# 505_outin_kinoma.net
KiCad netlist of a schematic drawn in EAGLE
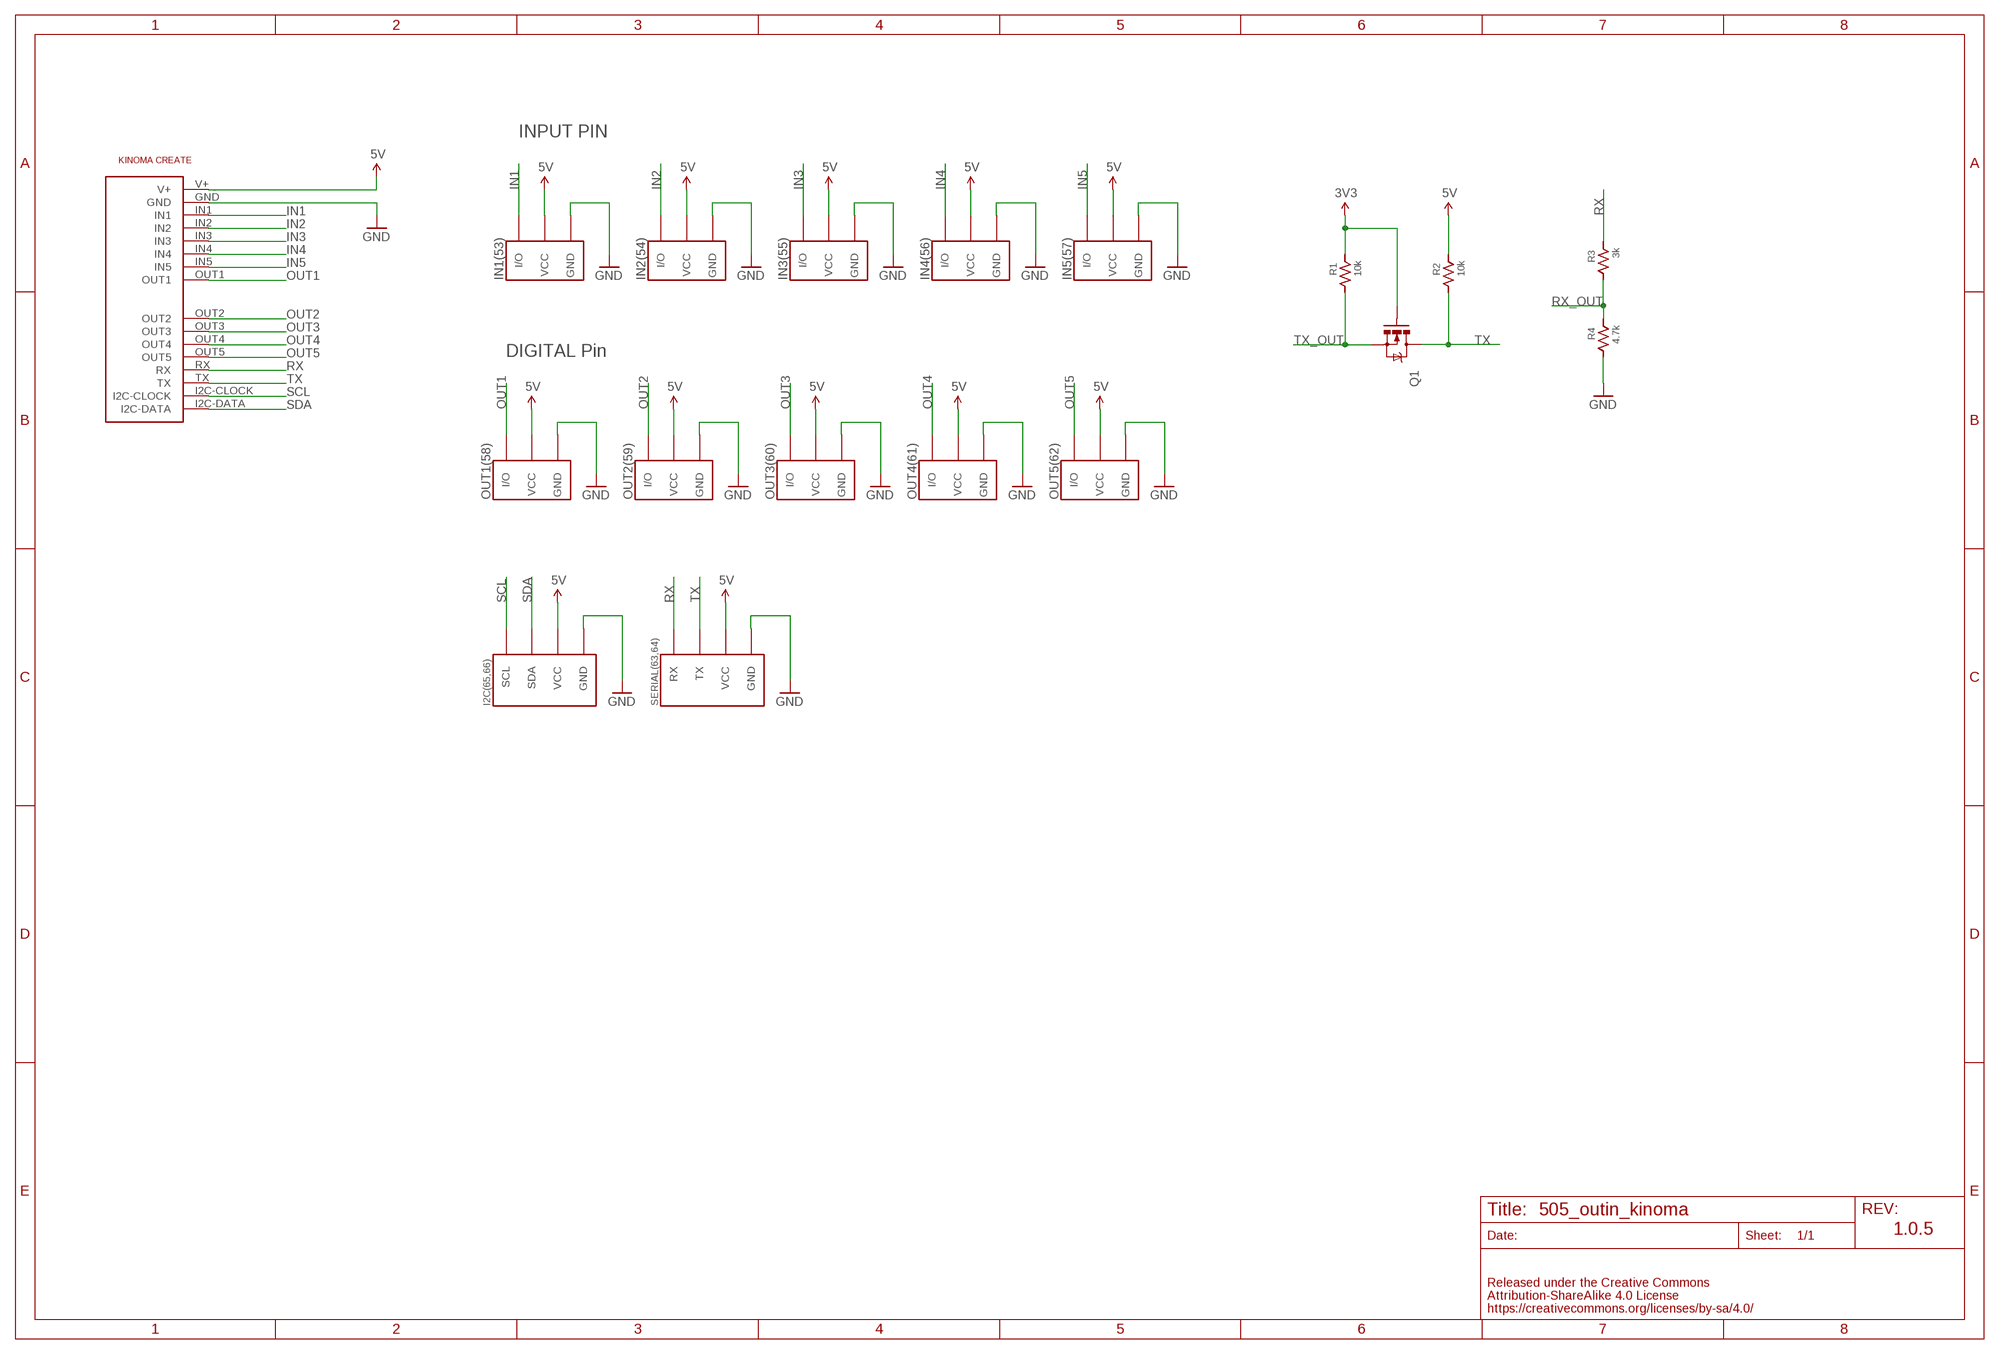
[diagram p0: schematic, sheet 1]

(export (version "E")
  (design (tool "Eeschema 10.0.6"))
  (components
    (comp (ref "I2C(65,66)")
      (value "I2C")
      (footprint "eagle-import:FABO_BRICK_I2C_S04B-PASK-2")
      (libsource (lib "eagle-import") (part "FABO_BRICK_I2C-S04B-PASK-2"))
    )
    (comp (ref "IN1(53)")
      (value "FABO_BRICK_3PIN-B03B-PASK-1")
      (footprint "eagle-import:FABO_BRICK_3PIN_B03B-PASK-1")
      (libsource (lib "eagle-import") (part "FABO_BRICK_3PIN-B03B-PASK-1"))
    )
    (comp (ref "IN2(54)")
      (value "FABO_BRICK_3PIN-B03B-PASK-1")
      (footprint "eagle-import:FABO_BRICK_3PIN_B03B-PASK-1")
      (libsource (lib "eagle-import") (part "FABO_BRICK_3PIN-B03B-PASK-1"))
    )
    (comp (ref "IN3(55)")
      (value "FABO_BRICK_3PIN-B03B-PASK-1")
      (footprint "eagle-import:FABO_BRICK_3PIN_B03B-PASK-1")
      (libsource (lib "eagle-import") (part "FABO_BRICK_3PIN-B03B-PASK-1"))
    )
    (comp (ref "IN4(56)")
      (value "FABO_BRICK_3PIN-B03B-PASK-1")
      (footprint "eagle-import:FABO_BRICK_3PIN_B03B-PASK-1")
      (libsource (lib "eagle-import") (part "FABO_BRICK_3PIN-B03B-PASK-1"))
    )
    (comp (ref "IN5(57)")
      (value "FABO_BRICK_3PIN-B03B-PASK-1")
      (footprint "eagle-import:FABO_BRICK_3PIN_B03B-PASK-1")
      (libsource (lib "eagle-import") (part "FABO_BRICK_3PIN-B03B-PASK-1"))
    )
    (comp (ref "OUT1(58)")
      (value "FABO_BRICK_3PIN-B03B-PASK-1")
      (footprint "eagle-import:FABO_BRICK_3PIN_B03B-PASK-1")
      (libsource (lib "eagle-import") (part "FABO_BRICK_3PIN-B03B-PASK-1"))
    )
    (comp (ref "OUT2(59)")
      (value "FABO_BRICK_3PIN-B03B-PASK-1")
      (footprint "eagle-import:FABO_BRICK_3PIN_B03B-PASK-1")
      (libsource (lib "eagle-import") (part "FABO_BRICK_3PIN-B03B-PASK-1"))
    )
    (comp (ref "OUT3(60)")
      (value "FABO_BRICK_3PIN-B03B-PASK-1")
      (footprint "eagle-import:FABO_BRICK_3PIN_B03B-PASK-1")
      (libsource (lib "eagle-import") (part "FABO_BRICK_3PIN-B03B-PASK-1"))
    )
    (comp (ref "OUT4(61)")
      (value "FABO_BRICK_3PIN-B03B-PASK-1")
      (footprint "eagle-import:FABO_BRICK_3PIN_B03B-PASK-1")
      (libsource (lib "eagle-import") (part "FABO_BRICK_3PIN-B03B-PASK-1"))
    )
    (comp (ref "OUT5(62)")
      (value "FABO_BRICK_3PIN-B03B-PASK-1")
      (footprint "eagle-import:FABO_BRICK_3PIN_B03B-PASK-1")
      (libsource (lib "eagle-import") (part "FABO_BRICK_3PIN-B03B-PASK-1"))
    )
    (comp (ref "Q1")
      (value "MOSFET-N-BSS138")
      (footprint "eagle-import:SOT23-3")
      (libsource (lib "eagle-import") (part "MOSFET-N-BSS138"))
    )
    (comp (ref "R1")
      (value "10k")
      (footprint "eagle-import:0402")
      (libsource (lib "eagle-import") (part "RESISTOR-0402"))
    )
    (comp (ref "R2")
      (value "10k")
      (footprint "eagle-import:0402")
      (libsource (lib "eagle-import") (part "RESISTOR-0402"))
    )
    (comp (ref "R3")
      (value "3k")
      (footprint "eagle-import:0402")
      (libsource (lib "eagle-import") (part "RESISTOR-0402"))
    )
    (comp (ref "R4")
      (value "4.7k")
      (footprint "eagle-import:0402")
      (libsource (lib "eagle-import") (part "RESISTOR-0402"))
    )
    (comp (ref "SERIAL(63,64)")
      (value "FABO_BRICK_SERIAL-S04B-PASK-2")
      (footprint "eagle-import:FABO_BRICK_SERIAL_S04B-PASK-2")
      (libsource (lib "eagle-import") (part "FABO_BRICK_SERIAL-S04B-PASK-2"))
    )
    (comp (ref "U$18")
      (value "FABO-KINOMA")
      (footprint "eagle-import:FABO-KINOMA")
      (libsource (lib "eagle-import") (part "FABO-KINOMA"))
    )
  )
  (nets
    (net (code "1") (name "/IN1") (class "Default")
      (node (ref "IN1(53)") (pin "I/O") (pinfunction "I/O_I/O") (pintype "bidirectional"))
      (node (ref "U$18") (pin "IN1") (pinfunction "IN1_IN1") (pintype "bidirectional"))
    )
    (net (code "2") (name "/IN2") (class "Default")
      (node (ref "IN2(54)") (pin "I/O") (pinfunction "I/O_I/O") (pintype "bidirectional"))
      (node (ref "U$18") (pin "IN2") (pinfunction "IN2_IN2") (pintype "bidirectional"))
    )
    (net (code "3") (name "/IN3") (class "Default")
      (node (ref "IN3(55)") (pin "I/O") (pinfunction "I/O_I/O") (pintype "bidirectional"))
      (node (ref "U$18") (pin "IN3") (pinfunction "IN3_IN3") (pintype "bidirectional"))
    )
    (net (code "4") (name "/IN4") (class "Default")
      (node (ref "IN4(56)") (pin "I/O") (pinfunction "I/O_I/O") (pintype "bidirectional"))
      (node (ref "U$18") (pin "IN4") (pinfunction "IN4_IN4") (pintype "bidirectional"))
    )
    (net (code "5") (name "/IN5") (class "Default")
      (node (ref "IN5(57)") (pin "I/O") (pinfunction "I/O_I/O") (pintype "bidirectional"))
      (node (ref "U$18") (pin "IN5") (pinfunction "IN5_IN5") (pintype "bidirectional"))
    )
    (net (code "6") (name "/OUT1") (class "Default")
      (node (ref "OUT1(58)") (pin "I/O") (pinfunction "I/O_I/O") (pintype "bidirectional"))
      (node (ref "U$18") (pin "OUT1") (pinfunction "OUT1_OUT1") (pintype "bidirectional"))
    )
    (net (code "7") (name "/OUT2") (class "Default")
      (node (ref "OUT2(59)") (pin "I/O") (pinfunction "I/O_I/O") (pintype "bidirectional"))
      (node (ref "U$18") (pin "OUT2") (pinfunction "OUT2_OUT2") (pintype "bidirectional"))
    )
    (net (code "8") (name "/OUT3") (class "Default")
      (node (ref "OUT3(60)") (pin "I/O") (pinfunction "I/O_I/O") (pintype "bidirectional"))
      (node (ref "U$18") (pin "OUT3") (pinfunction "OUT3_OUT3") (pintype "bidirectional"))
    )
    (net (code "9") (name "/OUT4") (class "Default")
      (node (ref "OUT4(61)") (pin "I/O") (pinfunction "I/O_I/O") (pintype "bidirectional"))
      (node (ref "U$18") (pin "OUT4") (pinfunction "OUT4_OUT4") (pintype "bidirectional"))
    )
    (net (code "10") (name "/OUT5") (class "Default")
      (node (ref "OUT5(62)") (pin "I/O") (pinfunction "I/O_I/O") (pintype "bidirectional"))
      (node (ref "U$18") (pin "OUT5") (pinfunction "OUT5_OUT5") (pintype "bidirectional"))
    )
    (net (code "11") (name "/RX") (class "Default")
      (node (ref "R3") (pin "P$2") (pinfunction "2_P$2") (pintype "bidirectional"))
      (node (ref "SERIAL(63,64)") (pin "RX") (pinfunction "RX_RX") (pintype "bidirectional"))
      (node (ref "U$18") (pin "RX") (pinfunction "RX_RX") (pintype "bidirectional"))
    )
    (net (code "12") (name "/RX_OUT") (class "Default")
      (node (ref "R3") (pin "P$1") (pinfunction "1_P$1") (pintype "bidirectional"))
      (node (ref "R4") (pin "P$2") (pinfunction "2_P$2") (pintype "bidirectional"))
    )
    (net (code "13") (name "/SCL") (class "Default")
      (node (ref "I2C(65,66)") (pin "SCL") (pinfunction "SCL_SCL") (pintype "bidirectional"))
      (node (ref "U$18") (pin "I2C-CLOCK") (pinfunction "I2C-CLOCK_I2C-CLOCK") (pintype "bidirectional"))
    )
    (net (code "14") (name "/SDA") (class "Default")
      (node (ref "I2C(65,66)") (pin "SDA") (pinfunction "SDA_SDA") (pintype "bidirectional"))
      (node (ref "U$18") (pin "I2C-DATA") (pinfunction "I2C-DATA_I2C-DATA") (pintype "bidirectional"))
    )
    (net (code "15") (name "/TX") (class "Default")
      (node (ref "Q1") (pin "3") (pinfunction "D_3") (pintype "passive"))
      (node (ref "R2") (pin "P$1") (pinfunction "1_P$1") (pintype "bidirectional"))
      (node (ref "SERIAL(63,64)") (pin "TX") (pinfunction "TX_TX") (pintype "bidirectional"))
      (node (ref "U$18") (pin "TX") (pinfunction "TX_TX") (pintype "bidirectional"))
    )
    (net (code "16") (name "/TX_OUT") (class "Default")
      (node (ref "Q1") (pin "2") (pinfunction "S_2") (pintype "passive"))
      (node (ref "R1") (pin "P$1") (pinfunction "1_P$1") (pintype "bidirectional"))
    )
    (net (code "17") (name "3V3") (class "Default")
      (node (ref "Q1") (pin "1") (pinfunction "G_1") (pintype "passive"))
      (node (ref "R1") (pin "P$2") (pinfunction "2_P$2") (pintype "bidirectional"))
    )
    (net (code "18") (name "5V") (class "Default")
      (node (ref "I2C(65,66)") (pin "VCC") (pinfunction "VCC_VCC") (pintype "bidirectional"))
      (node (ref "IN1(53)") (pin "VCC") (pinfunction "VCC_VCC") (pintype "bidirectional"))
      (node (ref "IN2(54)") (pin "VCC") (pinfunction "VCC_VCC") (pintype "bidirectional"))
      (node (ref "IN3(55)") (pin "VCC") (pinfunction "VCC_VCC") (pintype "bidirectional"))
      (node (ref "IN4(56)") (pin "VCC") (pinfunction "VCC_VCC") (pintype "bidirectional"))
      (node (ref "IN5(57)") (pin "VCC") (pinfunction "VCC_VCC") (pintype "bidirectional"))
      (node (ref "OUT1(58)") (pin "VCC") (pinfunction "VCC_VCC") (pintype "bidirectional"))
      (node (ref "OUT2(59)") (pin "VCC") (pinfunction "VCC_VCC") (pintype "bidirectional"))
      (node (ref "OUT3(60)") (pin "VCC") (pinfunction "VCC_VCC") (pintype "bidirectional"))
      (node (ref "OUT4(61)") (pin "VCC") (pinfunction "VCC_VCC") (pintype "bidirectional"))
      (node (ref "OUT5(62)") (pin "VCC") (pinfunction "VCC_VCC") (pintype "bidirectional"))
      (node (ref "R2") (pin "P$2") (pinfunction "2_P$2") (pintype "bidirectional"))
      (node (ref "SERIAL(63,64)") (pin "VCC") (pinfunction "VCC_VCC") (pintype "bidirectional"))
      (node (ref "U$18") (pin "V+") (pinfunction "V+_V+") (pintype "bidirectional"))
    )
    (net (code "19") (name "GND") (class "Default")
      (node (ref "I2C(65,66)") (pin "GND") (pinfunction "GND_GND") (pintype "bidirectional"))
      (node (ref "IN1(53)") (pin "GND") (pinfunction "GND_GND") (pintype "bidirectional"))
      (node (ref "IN2(54)") (pin "GND") (pinfunction "GND_GND") (pintype "bidirectional"))
      (node (ref "IN3(55)") (pin "GND") (pinfunction "GND_GND") (pintype "bidirectional"))
      (node (ref "IN4(56)") (pin "GND") (pinfunction "GND_GND") (pintype "bidirectional"))
      (node (ref "IN5(57)") (pin "GND") (pinfunction "GND_GND") (pintype "bidirectional"))
      (node (ref "OUT1(58)") (pin "GND") (pinfunction "GND_GND") (pintype "bidirectional"))
      (node (ref "OUT2(59)") (pin "GND") (pinfunction "GND_GND") (pintype "bidirectional"))
      (node (ref "OUT3(60)") (pin "GND") (pinfunction "GND_GND") (pintype "bidirectional"))
      (node (ref "OUT4(61)") (pin "GND") (pinfunction "GND_GND") (pintype "bidirectional"))
      (node (ref "OUT5(62)") (pin "GND") (pinfunction "GND_GND") (pintype "bidirectional"))
      (node (ref "R4") (pin "P$1") (pinfunction "1_P$1") (pintype "bidirectional"))
      (node (ref "SERIAL(63,64)") (pin "GND") (pinfunction "GND_GND") (pintype "bidirectional"))
      (node (ref "U$18") (pin "GND") (pinfunction "GND_GND") (pintype "bidirectional"))
    )
  )
)
